# BrainA1-11Nov2014.net
KiCad netlist of a schematic drawn in EAGLE
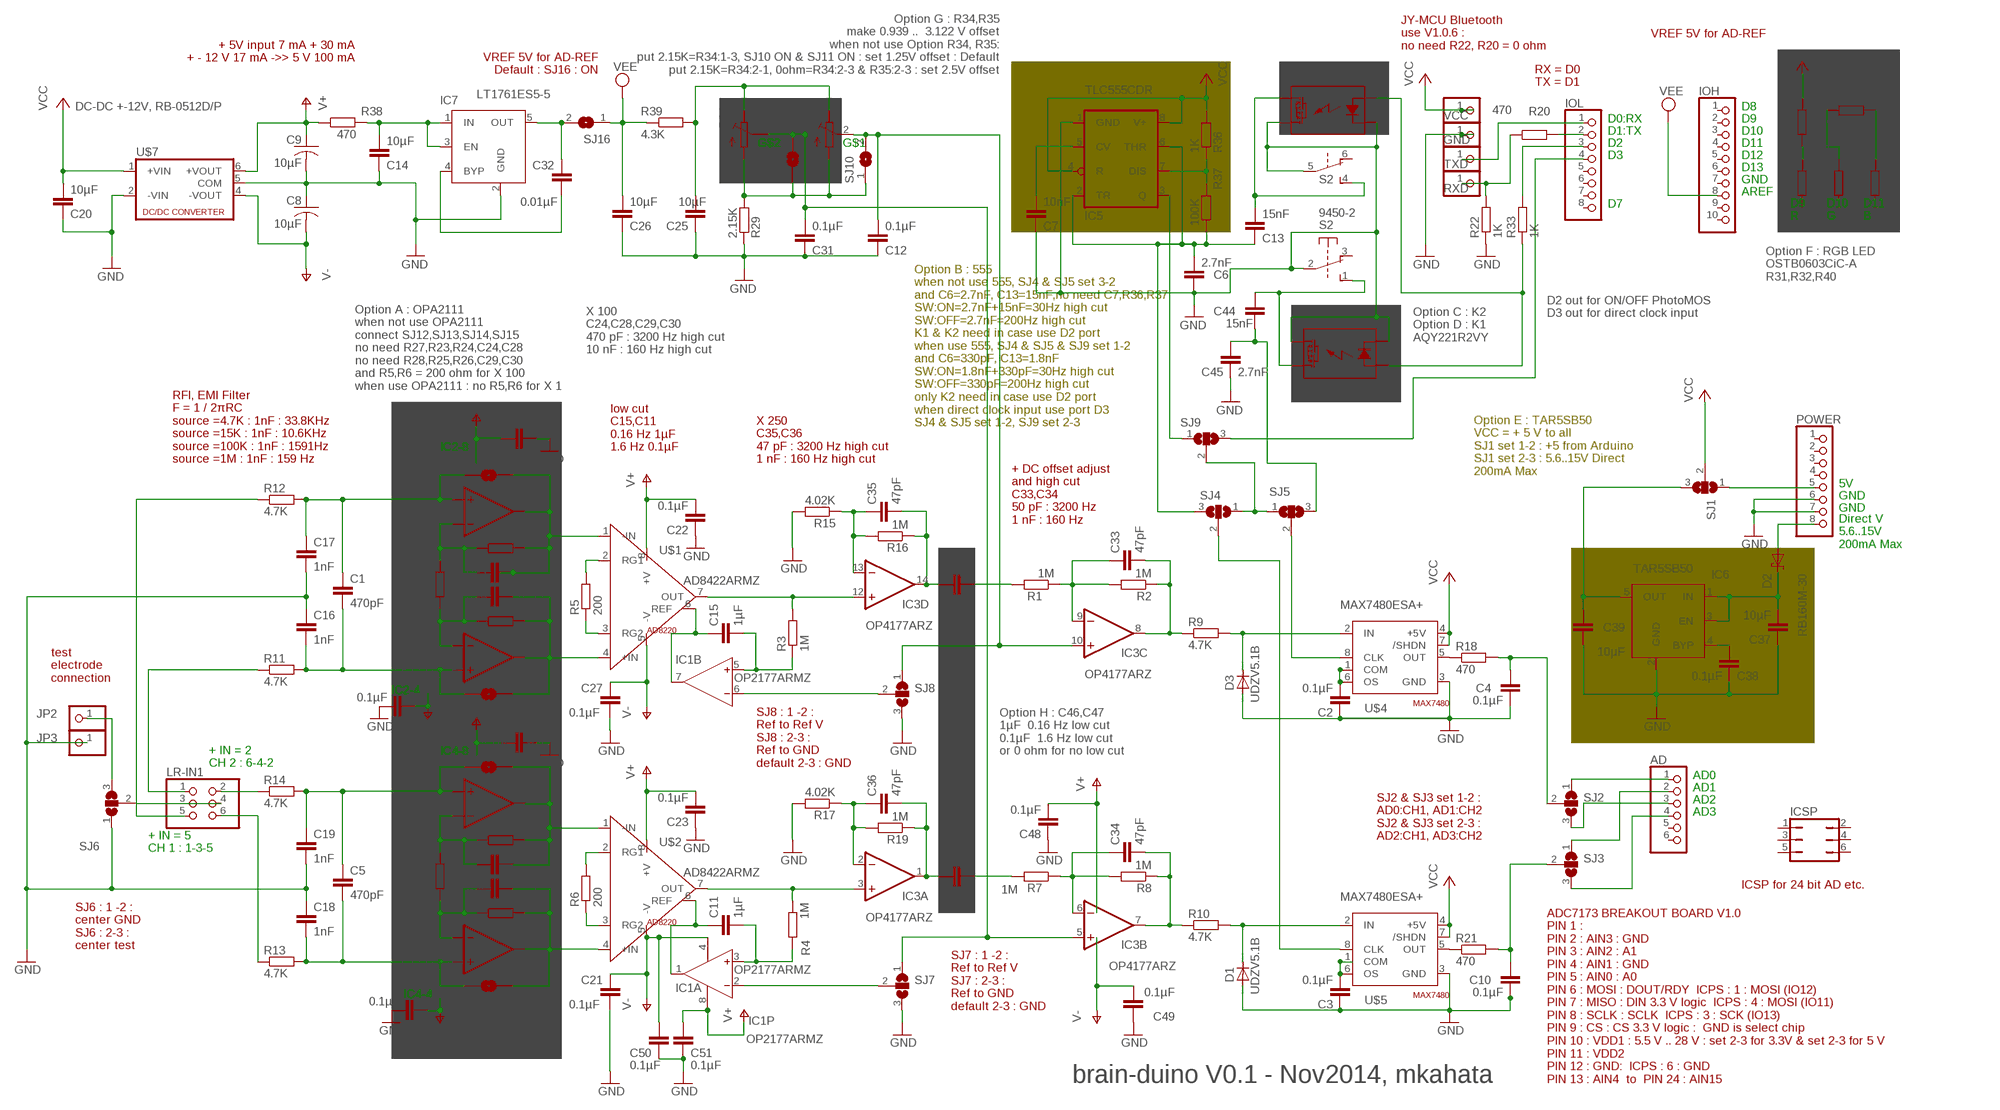
[diagram p0: schematic, sheet 1]

(export (version "E")
  (design (tool "Eeschema 10.0.6"))
  (components
    (comp (ref "AD")
      (value "PINHD-1X6")
      (footprint "eagle-import:1X06")
      (libsource (lib "eagle-import") (part "PINHD-1X6"))
    )
    (comp (ref "C1")
      (value "470pF")
      (footprint "eagle-import:C0805")
      (libsource (lib "eagle-import") (part "C-EUC0805"))
    )
    (comp (ref "C2")
      (value "0.1µF")
      (footprint "eagle-import:C0805")
      (libsource (lib "eagle-import") (part "C-EUC0805"))
    )
    (comp (ref "C3")
      (value "0.1µF")
      (footprint "eagle-import:C0805")
      (libsource (lib "eagle-import") (part "C-EUC0805"))
    )
    (comp (ref "C4")
      (value "0.1µF")
      (footprint "eagle-import:C0805")
      (libsource (lib "eagle-import") (part "C-EUC0805"))
    )
    (comp (ref "C5")
      (value "470pF")
      (footprint "eagle-import:C0805")
      (libsource (lib "eagle-import") (part "C-EUC0805"))
    )
    (comp (ref "C6")
      (value "2.7nF")
      (footprint "eagle-import:C0805")
      (libsource (lib "eagle-import") (part "C-EUC0805"))
    )
    (comp (ref "C7")
      (value "10nF")
      (footprint "eagle-import:C0805")
      (libsource (lib "eagle-import") (part "C-EUC0805"))
    )
    (comp (ref "C8")
      (value "10µF")
      (footprint "eagle-import:C0805")
      (libsource (lib "eagle-import") (part "C-USC0805"))
    )
    (comp (ref "C9")
      (value "10µF")
      (footprint "eagle-import:C0805")
      (libsource (lib "eagle-import") (part "C-USC0805"))
    )
    (comp (ref "C10")
      (value "0.1µF")
      (footprint "eagle-import:C0805")
      (libsource (lib "eagle-import") (part "C-EUC0805"))
    )
    (comp (ref "C11")
      (value "1µF")
      (footprint "eagle-import:C0805")
      (libsource (lib "eagle-import") (part "C-EUC0805"))
    )
    (comp (ref "C12")
      (value "0.1µF")
      (footprint "eagle-import:C0805")
      (libsource (lib "eagle-import") (part "C-EUC0805"))
    )
    (comp (ref "C13")
      (value "15nF")
      (footprint "eagle-import:C0805")
      (libsource (lib "eagle-import") (part "C-EUC0805"))
    )
    (comp (ref "C14")
      (value "10µF")
      (footprint "eagle-import:C0805")
      (libsource (lib "eagle-import") (part "C-EUC0805"))
    )
    (comp (ref "C15")
      (value "1µF")
      (footprint "eagle-import:C0805")
      (libsource (lib "eagle-import") (part "C-EUC0805"))
    )
    (comp (ref "C16")
      (value "1nF")
      (footprint "eagle-import:C0805")
      (libsource (lib "eagle-import") (part "C-EUC0805"))
    )
    (comp (ref "C17")
      (value "1nF")
      (footprint "eagle-import:C0805")
      (libsource (lib "eagle-import") (part "C-EUC0805"))
    )
    (comp (ref "C18")
      (value "1nF")
      (footprint "eagle-import:C0805")
      (libsource (lib "eagle-import") (part "C-EUC0805"))
    )
    (comp (ref "C19")
      (value "1nF")
      (footprint "eagle-import:C0805")
      (libsource (lib "eagle-import") (part "C-EUC0805"))
    )
    (comp (ref "C20")
      (value "10µF")
      (footprint "eagle-import:C0805")
      (libsource (lib "eagle-import") (part "C-EUC0805"))
    )
    (comp (ref "C21")
      (value "0.1µF")
      (footprint "eagle-import:C0805")
      (libsource (lib "eagle-import") (part "C-EUC0805"))
    )
    (comp (ref "C22")
      (value "0.1µF")
      (footprint "eagle-import:C0805")
      (libsource (lib "eagle-import") (part "C-EUC0805"))
    )
    (comp (ref "C23")
      (value "0.1µF")
      (footprint "eagle-import:C0805")
      (libsource (lib "eagle-import") (part "C-EUC0805"))
    )
    (comp (ref "C24")
      (value "470pF")
      (footprint "eagle-import:C0805")
      (libsource (lib "eagle-import") (part "C-EUC0805"))
    )
    (comp (ref "C25")
      (value "10µF")
      (footprint "eagle-import:C0805")
      (libsource (lib "eagle-import") (part "C-EUC0805"))
    )
    (comp (ref "C26")
      (value "10µF")
      (footprint "eagle-import:C0805")
      (libsource (lib "eagle-import") (part "C-EUC0805"))
    )
    (comp (ref "C27")
      (value "0.1µF")
      (footprint "eagle-import:C0805")
      (libsource (lib "eagle-import") (part "C-EUC0805"))
    )
    (comp (ref "C28")
      (value "470pF")
      (footprint "eagle-import:C0805")
      (libsource (lib "eagle-import") (part "C-EUC0805"))
    )
    (comp (ref "C29")
      (value "470pF")
      (footprint "eagle-import:C0805")
      (libsource (lib "eagle-import") (part "C-EUC0805"))
    )
    (comp (ref "C30")
      (value "470pF")
      (footprint "eagle-import:C0805")
      (libsource (lib "eagle-import") (part "C-EUC0805"))
    )
    (comp (ref "C31")
      (value "0.1µF")
      (footprint "eagle-import:C0805")
      (libsource (lib "eagle-import") (part "C-EUC0805"))
    )
    (comp (ref "C32")
      (value "0.01µF")
      (footprint "eagle-import:C0805")
      (libsource (lib "eagle-import") (part "C-EUC0805"))
    )
    (comp (ref "C33")
      (value "47pF")
      (footprint "eagle-import:C0805")
      (libsource (lib "eagle-import") (part "C-EUC0805"))
    )
    (comp (ref "C34")
      (value "47pF")
      (footprint "eagle-import:C0805")
      (libsource (lib "eagle-import") (part "C-EUC0805"))
    )
    (comp (ref "C35")
      (value "47pF")
      (footprint "eagle-import:C0805")
      (libsource (lib "eagle-import") (part "C-EUC0805"))
    )
    (comp (ref "C36")
      (value "47pF")
      (footprint "eagle-import:C0805")
      (libsource (lib "eagle-import") (part "C-EUC0805"))
    )
    (comp (ref "C37")
      (value "10µF")
      (footprint "eagle-import:C0805")
      (libsource (lib "eagle-import") (part "C-EUC0805"))
    )
    (comp (ref "C38")
      (value "0.1µF")
      (footprint "eagle-import:C0805")
      (libsource (lib "eagle-import") (part "C-EUC0805"))
    )
    (comp (ref "C39")
      (value "10µF")
      (footprint "eagle-import:C0805")
      (libsource (lib "eagle-import") (part "C-EUC0805"))
    )
    (comp (ref "C40")
      (value "0.1µF")
      (footprint "eagle-import:C0805")
      (libsource (lib "eagle-import") (part "C-EUC0805"))
    )
    (comp (ref "C41")
      (value "0.1µF")
      (footprint "eagle-import:C0805")
      (libsource (lib "eagle-import") (part "C-EUC0805"))
    )
    (comp (ref "C42")
      (value "0.1µF")
      (footprint "eagle-import:C0805")
      (libsource (lib "eagle-import") (part "C-EUC0805"))
    )
    (comp (ref "C43")
      (value "0.1µF")
      (footprint "eagle-import:C0805")
      (libsource (lib "eagle-import") (part "C-EUC0805"))
    )
    (comp (ref "C44")
      (value "15nF")
      (footprint "eagle-import:C0805")
      (libsource (lib "eagle-import") (part "C-EUC0805"))
    )
    (comp (ref "C45")
      (value "2.7nF")
      (footprint "eagle-import:C0805")
      (libsource (lib "eagle-import") (part "C-EUC0805"))
    )
    (comp (ref "C46")
      (value "1µF")
      (footprint "eagle-import:C0805")
      (libsource (lib "eagle-import") (part "C-EUC0805"))
    )
    (comp (ref "C47")
      (value "1µF")
      (footprint "eagle-import:C0805")
      (libsource (lib "eagle-import") (part "C-EUC0805"))
    )
    (comp (ref "C48")
      (value "0.1µF")
      (footprint "eagle-import:C0805")
      (libsource (lib "eagle-import") (part "C-EUC0805"))
    )
    (comp (ref "C49")
      (value "0.1µF")
      (footprint "eagle-import:C0805")
      (libsource (lib "eagle-import") (part "C-EUC0805"))
    )
    (comp (ref "C50")
      (value "0.1µF")
      (footprint "eagle-import:C0805")
      (libsource (lib "eagle-import") (part "C-EUC0805"))
    )
    (comp (ref "C51")
      (value "0.1µF")
      (footprint "eagle-import:C0805")
      (libsource (lib "eagle-import") (part "C-EUC0805"))
    )
    (comp (ref "D1")
      (value "UDZV5.1B")
      (footprint "eagle-import:SOD110-R")
      (libsource (lib "eagle-import") (part "DIODE-SOD110-R"))
    )
    (comp (ref "D2")
      (value "RB160M-30")
      (footprint "eagle-import:POWERDI323")
      (libsource (lib "eagle-import") (part "PD3S160"))
    )
    (comp (ref "D3")
      (value "UDZV5.1B")
      (footprint "eagle-import:SOD110-R")
      (libsource (lib "eagle-import") (part "DIODE-SOD110-R"))
    )
    (comp (ref "GND")
      (value "PINHD-1X1")
      (footprint "eagle-import:1X01")
      (libsource (lib "eagle-import") (part "PINHD-1X1"))
    )
    (comp (ref "IC1")
      (value "OP2177ARMZ")
      (footprint "eagle-import:MSOP08")
      (fields (field (name "MPN") "AD8656ARMZ"))
      (libsource (lib "eagle-import") (part "AD8656RM"))
    )
    (comp (ref "IC2")
      (value "OPA2111KP")
      (footprint "eagle-import:DIL08")
      (libsource (lib "eagle-import") (part "OPA2111P"))
    )
    (comp (ref "IC3")
      (value "OP4177ARZ")
      (footprint "eagle-import:SO14")
      (libsource (lib "eagle-import") (part "TL064D"))
    )
    (comp (ref "IC4")
      (value "OPA2111KP")
      (footprint "eagle-import:DIL08")
      (libsource (lib "eagle-import") (part "OPA2111P"))
    )
    (comp (ref "IC5")
      (value "TLC555CDR")
      (footprint "eagle-import:SO08")
      (libsource (lib "eagle-import") (part "555DLM"))
    )
    (comp (ref "IC6")
      (value "TAR5SB50")
      (footprint "eagle-import:SOT23-5")
      (libsource (lib "eagle-import") (part "MIC5219XX"))
    )
    (comp (ref "IC7")
      (value "LT1761ES5-5")
      (footprint "eagle-import:SOT23-5")
      (libsource (lib "eagle-import") (part "MIC5219XX"))
    )
    (comp (ref "ICSP")
      (value "JP3Q")
      (footprint "eagle-import:JP3Q")
      (libsource (lib "eagle-import") (part "JP3Q"))
    )
    (comp (ref "IOH")
      (value "PINHD-1X10")
      (footprint "eagle-import:1X10")
      (libsource (lib "eagle-import") (part "PINHD-1X10"))
    )
    (comp (ref "IOL")
      (value "PINHD-1X8")
      (footprint "eagle-import:1X08")
      (libsource (lib "eagle-import") (part "PINHD-1X8"))
    )
    (comp (ref "JP2")
      (value "PINHD-1X1")
      (footprint "eagle-import:1X01")
      (libsource (lib "eagle-import") (part "PINHD-1X1"))
    )
    (comp (ref "JP3")
      (value "PINHD-1X1")
      (footprint "eagle-import:1X01")
      (libsource (lib "eagle-import") (part "PINHD-1X1"))
    )
    (comp (ref "K1")
      (value "AQY221R2VY")
      (footprint "eagle-import:SSOP4")
      (fields (field (name "MF") "AROMAT/ MATSUSHITA") (field (name "MPN") "AQY221R2V"))
      (libsource (lib "eagle-import") (part "AQY2212VR"))
    )
    (comp (ref "K2")
      (value "AQY221R2VY")
      (footprint "eagle-import:SSOP4")
      (fields (field (name "MF") "AROMAT/ MATSUSHITA") (field (name "MPN") "AQY221R2V"))
      (libsource (lib "eagle-import") (part "AQY2212VR"))
    )
    (comp (ref "LR-IN1")
      (value "PINHD-2X3/90")
      (footprint "eagle-import:2X03_90")
      (libsource (lib "eagle-import") (part "PINHD-2X3/90"))
    )
    (comp (ref "POWER")
      (value "PINHD-1X8")
      (footprint "eagle-import:1X08")
      (libsource (lib "eagle-import") (part "PINHD-1X8"))
    )
    (comp (ref "R1")
      (value "1M")
      (footprint "eagle-import:R0805")
      (libsource (lib "eagle-import") (part "R-EU_R0805"))
    )
    (comp (ref "R2")
      (value "1M")
      (footprint "eagle-import:R0805")
      (libsource (lib "eagle-import") (part "R-EU_R0805"))
    )
    (comp (ref "R3")
      (value "1M")
      (footprint "eagle-import:R0805")
      (libsource (lib "eagle-import") (part "R-EU_R0805"))
    )
    (comp (ref "R4")
      (value "1M")
      (footprint "eagle-import:R0805")
      (libsource (lib "eagle-import") (part "R-EU_R0805"))
    )
    (comp (ref "R5")
      (value "200")
      (footprint "eagle-import:R0805")
      (libsource (lib "eagle-import") (part "R-EU_R0805"))
    )
    (comp (ref "R6")
      (value "200")
      (footprint "eagle-import:R0805")
      (libsource (lib "eagle-import") (part "R-EU_R0805"))
    )
    (comp (ref "R7")
      (value "1M")
      (footprint "eagle-import:R0805")
      (libsource (lib "eagle-import") (part "R-EU_R0805"))
    )
    (comp (ref "R8")
      (value "1M")
      (footprint "eagle-import:R0805")
      (libsource (lib "eagle-import") (part "R-EU_R0805"))
    )
    (comp (ref "R9")
      (value "4.7K")
      (footprint "eagle-import:R0805")
      (libsource (lib "eagle-import") (part "R-EU_R0805"))
    )
    (comp (ref "R10")
      (value "4.7K")
      (footprint "eagle-import:R0805")
      (libsource (lib "eagle-import") (part "R-EU_R0805"))
    )
    (comp (ref "R11")
      (value "4.7K")
      (footprint "eagle-import:R0805")
      (libsource (lib "eagle-import") (part "R-EU_R0805"))
    )
    (comp (ref "R12")
      (value "4.7K")
      (footprint "eagle-import:R0805")
      (libsource (lib "eagle-import") (part "R-EU_R0805"))
    )
    (comp (ref "R13")
      (value "4.7K")
      (footprint "eagle-import:R0805")
      (libsource (lib "eagle-import") (part "R-EU_R0805"))
    )
    (comp (ref "R14")
      (value "4.7K")
      (footprint "eagle-import:R0805")
      (libsource (lib "eagle-import") (part "R-EU_R0805"))
    )
    (comp (ref "R15")
      (value "4.02K")
      (footprint "eagle-import:R0805")
      (libsource (lib "eagle-import") (part "R-EU_R0805"))
    )
    (comp (ref "R16")
      (value "1M")
      (footprint "eagle-import:R0805")
      (libsource (lib "eagle-import") (part "R-EU_R0805"))
    )
    (comp (ref "R17")
      (value "4.02K")
      (footprint "eagle-import:R0805")
      (libsource (lib "eagle-import") (part "R-EU_R0805"))
    )
    (comp (ref "R18")
      (value "470")
      (footprint "eagle-import:R0805")
      (libsource (lib "eagle-import") (part "R-EU_R0805"))
    )
    (comp (ref "R19")
      (value "1M")
      (footprint "eagle-import:R0805")
      (libsource (lib "eagle-import") (part "R-EU_R0805"))
    )
    (comp (ref "R20")
      (value "470")
      (footprint "eagle-import:R0805")
      (libsource (lib "eagle-import") (part "R-EU_R0805"))
    )
    (comp (ref "R21")
      (value "470")
      (footprint "eagle-import:R0805")
      (libsource (lib "eagle-import") (part "R-EU_R0805"))
    )
    (comp (ref "R22")
      (value "1K")
      (footprint "eagle-import:R0805")
      (libsource (lib "eagle-import") (part "R-EU_R0805"))
    )
    (comp (ref "R23")
      (value "100K")
      (footprint "eagle-import:R0805")
      (libsource (lib "eagle-import") (part "R-EU_R0805"))
    )
    (comp (ref "R24")
      (value "100K")
      (footprint "eagle-import:R0805")
      (libsource (lib "eagle-import") (part "R-EU_R0805"))
    )
    (comp (ref "R25")
      (value "100K")
      (footprint "eagle-import:R0805")
      (libsource (lib "eagle-import") (part "R-EU_R0805"))
    )
    (comp (ref "R26")
      (value "100K")
      (footprint "eagle-import:R0805")
      (libsource (lib "eagle-import") (part "R-EU_R0805"))
    )
    (comp (ref "R27")
      (value "2K")
      (footprint "eagle-import:R0805")
      (libsource (lib "eagle-import") (part "R-EU_R0805"))
    )
    (comp (ref "R28")
      (value "2K")
      (footprint "eagle-import:R0805")
      (libsource (lib "eagle-import") (part "R-EU_R0805"))
    )
    (comp (ref "R29")
      (value "2.15K")
      (footprint "eagle-import:R0805")
      (libsource (lib "eagle-import") (part "R-EU_R0805"))
    )
    (comp (ref "R30")
      (value "LED")
      (footprint "eagle-import:R0402")
      (libsource (lib "eagle-import") (part "R-EU_R0402"))
    )
    (comp (ref "R31")
      (value "1K")
      (footprint "eagle-import:R0402")
      (libsource (lib "eagle-import") (part "R-EU_R0402"))
    )
    (comp (ref "R32")
      (value "1K")
      (footprint "eagle-import:R0402")
      (libsource (lib "eagle-import") (part "R-EU_R0402"))
    )
    (comp (ref "R33")
      (value "1K")
      (footprint "eagle-import:R0805")
      (libsource (lib "eagle-import") (part "R-EU_R0805"))
    )
    (comp (ref "R34")
      (value "10K")
      (footprint "eagle-import:RTRIM5X")
      (libsource (lib "eagle-import") (part "R-TRIMM5X"))
    )
    (comp (ref "R35")
      (value "10K")
      (footprint "eagle-import:RTRIM5X")
      (libsource (lib "eagle-import") (part "R-TRIMM5X"))
    )
    (comp (ref "R36")
      (value "1K")
      (footprint "eagle-import:R0805")
      (libsource (lib "eagle-import") (part "R-EU_R0805"))
    )
    (comp (ref "R37")
      (value "100K")
      (footprint "eagle-import:R0805")
      (libsource (lib "eagle-import") (part "R-EU_R0805"))
    )
    (comp (ref "R38")
      (value "470")
      (footprint "eagle-import:R0805")
      (libsource (lib "eagle-import") (part "R-EU_R0805"))
    )
    (comp (ref "R39")
      (value "4.3K")
      (footprint "eagle-import:R0805")
      (libsource (lib "eagle-import") (part "R-EU_R0805"))
    )
    (comp (ref "R40")
      (value "1K")
      (footprint "eagle-import:R0402")
      (libsource (lib "eagle-import") (part "R-EU_R0402"))
    )
    (comp (ref "R41")
      (value "LED")
      (footprint "eagle-import:R0402")
      (libsource (lib "eagle-import") (part "R-EU_R0402"))
    )
    (comp (ref "RXD")
      (value "PINHD-1X1")
      (footprint "eagle-import:1X01")
      (libsource (lib "eagle-import") (part "PINHD-1X1"))
    )
    (comp (ref "S2")
      (value "9450-2")
      (footprint "eagle-import:9450-2")
      (libsource (lib "eagle-import") (part "9450-2"))
    )
    (comp (ref "SJ1")
      (value "SJ2W")
      (footprint "eagle-import:SJ_2")
      (libsource (lib "eagle-import") (part "SJ2W"))
    )
    (comp (ref "SJ2")
      (value "SJ2W")
      (footprint "eagle-import:SJ_2")
      (libsource (lib "eagle-import") (part "SJ2W"))
    )
    (comp (ref "SJ3")
      (value "SJ2W")
      (footprint "eagle-import:SJ_2")
      (libsource (lib "eagle-import") (part "SJ2W"))
    )
    (comp (ref "SJ4")
      (value "SJ2W")
      (footprint "eagle-import:SJ_2")
      (libsource (lib "eagle-import") (part "SJ2W"))
    )
    (comp (ref "SJ5")
      (value "SJ2W")
      (footprint "eagle-import:SJ_2")
      (libsource (lib "eagle-import") (part "SJ2W"))
    )
    (comp (ref "SJ6")
      (value "SJ2W")
      (footprint "eagle-import:SJ_2")
      (libsource (lib "eagle-import") (part "SJ2W"))
    )
    (comp (ref "SJ7")
      (value "SJ2W")
      (footprint "eagle-import:SJ_2")
      (libsource (lib "eagle-import") (part "SJ2W"))
    )
    (comp (ref "SJ8")
      (value "SJ2W")
      (footprint "eagle-import:SJ_2")
      (libsource (lib "eagle-import") (part "SJ2W"))
    )
    (comp (ref "SJ9")
      (value "SJ2W")
      (footprint "eagle-import:SJ_2")
      (libsource (lib "eagle-import") (part "SJ2W"))
    )
    (comp (ref "SJ10")
      (value "SJ")
      (footprint "eagle-import:SJ")
      (libsource (lib "eagle-import") (part "SJ"))
    )
    (comp (ref "SJ11")
      (value "SJ")
      (footprint "eagle-import:SJ")
      (libsource (lib "eagle-import") (part "SJ"))
    )
    (comp (ref "SJ12")
      (value "SJ")
      (footprint "eagle-import:SJ")
      (libsource (lib "eagle-import") (part "SJ"))
    )
    (comp (ref "SJ13")
      (value "SJ")
      (footprint "eagle-import:SJ")
      (libsource (lib "eagle-import") (part "SJ"))
    )
    (comp (ref "SJ14")
      (value "SJ")
      (footprint "eagle-import:SJ")
      (libsource (lib "eagle-import") (part "SJ"))
    )
    (comp (ref "SJ15")
      (value "SJ")
      (footprint "eagle-import:SJ")
      (libsource (lib "eagle-import") (part "SJ"))
    )
    (comp (ref "SJ16")
      (value "SJ")
      (footprint "eagle-import:SJ")
      (libsource (lib "eagle-import") (part "SJ"))
    )
    (comp (ref "TXD")
      (value "PINHD-1X1")
      (footprint "eagle-import:1X01")
      (libsource (lib "eagle-import") (part "PINHD-1X1"))
    )
    (comp (ref "U$1")
      (value "AD8422ARMZ")
      (footprint "eagle-import:AD8220")
      (libsource (lib "eagle-import") (part "AD8220"))
    )
    (comp (ref "U$2")
      (value "AD8422ARMZ")
      (footprint "eagle-import:AD8220")
      (libsource (lib "eagle-import") (part "AD8220"))
    )
    (comp (ref "U$4")
      (value "MAX7480ESA+")
      (footprint "eagle-import:MAX7480")
      (libsource (lib "eagle-import") (part "MAX7480"))
    )
    (comp (ref "U$5")
      (value "MAX7480ESA+")
      (footprint "eagle-import:MAX7480")
      (libsource (lib "eagle-import") (part "MAX7480"))
    )
    (comp (ref "U$7")
      (value "DC-DC +-12V, RB-0512D/P")
      (footprint "eagle-import:RB-0515D")
      (libsource (lib "eagle-import") (part "RB-0515D"))
    )
    (comp (ref "VCC")
      (value "PINHD-1X1")
      (footprint "eagle-import:1X01")
      (libsource (lib "eagle-import") (part "PINHD-1X1"))
    )
  )
  (nets
    (net (code "1") (name "GND") (class "Default")
      (node (ref "C10") (pin "1") (pinfunction "1_1") (pintype "passive"))
      (node (ref "C12") (pin "1") (pinfunction "1_1") (pintype "passive"))
      (node (ref "C14") (pin "1") (pinfunction "1_1") (pintype "passive"))
      (node (ref "C16") (pin "1") (pinfunction "1_1") (pintype "passive"))
      (node (ref "C17") (pin "2") (pinfunction "2_2") (pintype "passive"))
      (node (ref "C18") (pin "1") (pinfunction "1_1") (pintype "passive"))
      (node (ref "C19") (pin "2") (pinfunction "2_2") (pintype "passive"))
      (node (ref "C2") (pin "1") (pinfunction "1_1") (pintype "passive"))
      (node (ref "C20") (pin "1") (pinfunction "1_1") (pintype "passive"))
      (node (ref "C21") (pin "2") (pinfunction "2_2") (pintype "passive"))
      (node (ref "C22") (pin "1") (pinfunction "1_1") (pintype "passive"))
      (node (ref "C23") (pin "1") (pinfunction "1_1") (pintype "passive"))
      (node (ref "C25") (pin "1") (pinfunction "1_1") (pintype "passive"))
      (node (ref "C26") (pin "1") (pinfunction "1_1") (pintype "passive"))
      (node (ref "C27") (pin "2") (pinfunction "2_2") (pintype "passive"))
      (node (ref "C3") (pin "1") (pinfunction "1_1") (pintype "passive"))
      (node (ref "C31") (pin "1") (pinfunction "1_1") (pintype "passive"))
      (node (ref "C37") (pin "1") (pinfunction "1_1") (pintype "passive"))
      (node (ref "C38") (pin "1") (pinfunction "1_1") (pintype "passive"))
      (node (ref "C39") (pin "1") (pinfunction "1_1") (pintype "passive"))
      (node (ref "C4") (pin "1") (pinfunction "1_1") (pintype "passive"))
      (node (ref "C40") (pin "1") (pinfunction "1_1") (pintype "passive"))
      (node (ref "C41") (pin "2") (pinfunction "2_2") (pintype "passive"))
      (node (ref "C42") (pin "2") (pinfunction "2_2") (pintype "passive"))
      (node (ref "C43") (pin "2") (pinfunction "2_2") (pintype "passive"))
      (node (ref "C45") (pin "1") (pinfunction "1_1") (pintype "passive"))
      (node (ref "C48") (pin "1") (pinfunction "1_1") (pintype "passive"))
      (node (ref "C49") (pin "1") (pinfunction "1_1") (pintype "passive"))
      (node (ref "C50") (pin "2") (pinfunction "2_2") (pintype "passive"))
      (node (ref "C51") (pin "2") (pinfunction "2_2") (pintype "passive"))
      (node (ref "C6") (pin "1") (pinfunction "1_1") (pintype "passive"))
      (node (ref "C7") (pin "1") (pinfunction "1_1") (pintype "passive"))
      (node (ref "C8") (pin "1") (pinfunction "1_1") (pintype "passive"))
      (node (ref "C9") (pin "2") (pinfunction "2_2") (pintype "passive"))
      (node (ref "D1") (pin "A") (pinfunction "A_A") (pintype "passive"))
      (node (ref "D3") (pin "A") (pinfunction "A_A") (pintype "passive"))
      (node (ref "GND") (pin "1") (pinfunction "1_1") (pintype "passive"))
      (node (ref "IC5") (pin "1") (pinfunction "GND_1") (pintype "power_in"))
      (node (ref "IC6") (pin "2") (pinfunction "GND_2") (pintype "power_in"))
      (node (ref "IC7") (pin "2") (pinfunction "GND_2") (pintype "power_in"))
      (node (ref "JP3") (pin "1") (pinfunction "1_1") (pintype "passive"))
      (node (ref "K1") (pin "2") (pinfunction "K_2") (pintype "passive"))
      (node (ref "K1") (pin "3") (pinfunction "DS2_3") (pintype "passive"))
      (node (ref "K2") (pin "2") (pinfunction "K_2") (pintype "passive"))
      (node (ref "K2") (pin "3") (pinfunction "DS2_3") (pintype "passive"))
      (node (ref "POWER") (pin "6") (pinfunction "6_6") (pintype "passive"))
      (node (ref "POWER") (pin "7") (pinfunction "7_7") (pintype "passive"))
      (node (ref "R15") (pin "2") (pinfunction "2_2") (pintype "passive"))
      (node (ref "R17") (pin "2") (pinfunction "2_2") (pintype "passive"))
      (node (ref "R22") (pin "1") (pinfunction "1_1") (pintype "passive"))
      (node (ref "R29") (pin "1") (pinfunction "1_1") (pintype "passive"))
      (node (ref "S2") (pin "2") (pinfunction "P_2") (pintype "passive"))
      (node (ref "S2") (pin "5") (pinfunction "P_5") (pintype "passive"))
      (node (ref "SJ6") (pin "1") (pinfunction "1_1") (pintype "passive"))
      (node (ref "SJ7") (pin "3") (pinfunction "3_3") (pintype "passive"))
      (node (ref "SJ8") (pin "3") (pinfunction "3_3") (pintype "passive"))
      (node (ref "U$4") (pin "3") (pinfunction "GND_3") (pintype "power_in"))
      (node (ref "U$5") (pin "3") (pinfunction "GND_3") (pintype "power_in"))
      (node (ref "U$7") (pin "2") (pinfunction "-VIN_2") (pintype "passive"))
      (node (ref "U$7") (pin "5") (pinfunction "COM_5") (pintype "passive"))
    )
    (net (code "2") (name "Net-(AD-Pad1)") (class "Default")
      (node (ref "AD") (pin "1") (pinfunction "1_1") (pintype "passive"))
      (node (ref "SJ2") (pin "1") (pinfunction "1_1") (pintype "passive"))
    )
    (net (code "3") (name "Net-(AD-Pad2)") (class "Default")
      (node (ref "AD") (pin "2") (pinfunction "2_2") (pintype "passive"))
      (node (ref "SJ3") (pin "1") (pinfunction "1_1") (pintype "passive"))
    )
    (net (code "4") (name "Net-(AD-Pad3)") (class "Default")
      (node (ref "AD") (pin "3") (pinfunction "3_3") (pintype "passive"))
      (node (ref "SJ2") (pin "3") (pinfunction "3_3") (pintype "passive"))
    )
    (net (code "5") (name "Net-(AD-Pad4)") (class "Default")
      (node (ref "AD") (pin "4") (pinfunction "4_4") (pintype "passive"))
      (node (ref "SJ3") (pin "3") (pinfunction "3_3") (pintype "passive"))
    )
    (net (code "6") (name "Net-(C4-Pad2)") (class "Default")
      (node (ref "C4") (pin "2") (pinfunction "2_2") (pintype "passive"))
      (node (ref "R18") (pin "2") (pinfunction "2_2") (pintype "passive"))
      (node (ref "SJ2") (pin "2") (pinfunction "2_2") (pintype "passive"))
    )
    (net (code "7") (name "Net-(C10-Pad2)") (class "Default")
      (node (ref "C10") (pin "2") (pinfunction "2_2") (pintype "passive"))
      (node (ref "R21") (pin "2") (pinfunction "2_2") (pintype "passive"))
      (node (ref "SJ3") (pin "2") (pinfunction "2_2") (pintype "passive"))
    )
    (net (code "8") (name "Net-(C44-Pad1)") (class "Default")
      (node (ref "C44") (pin "1") (pinfunction "1_1") (pintype "passive"))
      (node (ref "C45") (pin "2") (pinfunction "2_2") (pintype "passive"))
      (node (ref "SJ5") (pin "3") (pinfunction "3_3") (pintype "passive"))
    )
    (net (code "9") (name "Net-(C46-Pad2)") (class "Default")
      (node (ref "C46") (pin "2") (pinfunction "2_2") (pintype "passive"))
      (node (ref "R1") (pin "2") (pinfunction "2_2") (pintype "passive"))
    )
    (net (code "10") (name "Net-(C47-Pad2)") (class "Default")
      (node (ref "C47") (pin "2") (pinfunction "2_2") (pintype "passive"))
      (node (ref "R7") (pin "2") (pinfunction "2_2") (pintype "passive"))
    )
    (net (code "11") (name "Net-(D2-PadA)") (class "Default")
      (node (ref "D2") (pin "A") (pinfunction "A_A") (pintype "passive"))
      (node (ref "POWER") (pin "8") (pinfunction "8_8") (pintype "passive"))
    )
    (net (code "12") (name "Net-(IC1A-IN+)") (class "Default")
      (node (ref "C11") (pin "2") (pinfunction "2_2") (pintype "passive"))
      (node (ref "IC1") (pin "3") (pinfunction "IN+_3") (pintype "input"))
      (node (ref "R4") (pin "1") (pinfunction "1_1") (pintype "passive"))
    )
    (net (code "13") (name "Net-(IC1A-IN-)") (class "Default")
      (node (ref "IC1") (pin "2") (pinfunction "IN-_2") (pintype "input"))
      (node (ref "SJ7") (pin "2") (pinfunction "2_2") (pintype "passive"))
    )
    (net (code "14") (name "Net-(IC1A-OUT)") (class "Default")
      (node (ref "C11") (pin "1") (pinfunction "1_1") (pintype "passive"))
      (node (ref "IC1") (pin "1") (pinfunction "OUT_1") (pintype "output"))
      (node (ref "U$2") (pin "6") (pinfunction "REF_6") (pintype "input"))
    )
    (net (code "15") (name "Net-(IC1B-IN+)") (class "Default")
      (node (ref "C15") (pin "2") (pinfunction "2_2") (pintype "passive"))
      (node (ref "IC1") (pin "5") (pinfunction "IN+_5") (pintype "input"))
      (node (ref "R3") (pin "1") (pinfunction "1_1") (pintype "passive"))
    )
    (net (code "16") (name "Net-(IC1B-IN-)") (class "Default")
      (node (ref "IC1") (pin "6") (pinfunction "IN-_6") (pintype "input"))
      (node (ref "SJ8") (pin "2") (pinfunction "2_2") (pintype "passive"))
    )
    (net (code "17") (name "Net-(IC1B-OUT)") (class "Default")
      (node (ref "C15") (pin "1") (pinfunction "1_1") (pintype "passive"))
      (node (ref "IC1") (pin "7") (pinfunction "OUT_7") (pintype "output"))
      (node (ref "U$1") (pin "6") (pinfunction "REF_6") (pintype "input"))
    )
    (net (code "18") (name "Net-(IC2A-+IN)") (class "Default")
      (node (ref "C1") (pin "1") (pinfunction "1_1") (pintype "passive"))
      (node (ref "C17") (pin "1") (pinfunction "1_1") (pintype "passive"))
      (node (ref "IC2") (pin "3") (pinfunction "+IN_3") (pintype "input"))
      (node (ref "R12") (pin "2") (pinfunction "2_2") (pintype "passive"))
      (node (ref "SJ12") (pin "2") (pinfunction "2_2") (pintype "passive"))
    )
    (net (code "19") (name "Net-(IC2A--IN)") (class "Default")
      (node (ref "C24") (pin "1") (pinfunction "1_1") (pintype "passive"))
      (node (ref "IC2") (pin "2") (pinfunction "-IN_2") (pintype "input"))
      (node (ref "R23") (pin "1") (pinfunction "1_1") (pintype "passive"))
      (node (ref "R27") (pin "2") (pinfunction "2_2") (pintype "passive"))
    )
    (net (code "20") (name "Net-(IC2A-OUT)") (class "Default")
      (node (ref "C24") (pin "2") (pinfunction "2_2") (pintype "passive"))
      (node (ref "IC2") (pin "1") (pinfunction "OUT_1") (pintype "output"))
      (node (ref "R23") (pin "2") (pinfunction "2_2") (pintype "passive"))
      (node (ref "SJ12") (pin "1") (pinfunction "1_1") (pintype "passive"))
      (node (ref "U$1") (pin "1") (pinfunction "-IN_1") (pintype "input"))
    )
    (net (code "21") (name "Net-(IC2B-+IN)") (class "Default")
      (node (ref "C1") (pin "2") (pinfunction "2_2") (pintype "passive"))
      (node (ref "C16") (pin "2") (pinfunction "2_2") (pintype "passive"))
      (node (ref "IC2") (pin "5") (pinfunction "+IN_5") (pintype "input"))
      (node (ref "R11") (pin "2") (pinfunction "2_2") (pintype "passive"))
      (node (ref "SJ13") (pin "2") (pinfunction "2_2") (pintype "passive"))
    )
    (net (code "22") (name "Net-(IC2B--IN)") (class "Default")
      (node (ref "C28") (pin "1") (pinfunction "1_1") (pintype "passive"))
      (node (ref "IC2") (pin "6") (pinfunction "-IN_6") (pintype "input"))
      (node (ref "R24") (pin "1") (pinfunction "1_1") (pintype "passive"))
      (node (ref "R27") (pin "1") (pinfunction "1_1") (pintype "passive"))
    )
    (net (code "23") (name "Net-(IC2B-OUT)") (class "Default")
      (node (ref "C28") (pin "2") (pinfunction "2_2") (pintype "passive"))
      (node (ref "IC2") (pin "7") (pinfunction "OUT_7") (pintype "output"))
      (node (ref "R24") (pin "2") (pinfunction "2_2") (pintype "passive"))
      (node (ref "SJ13") (pin "1") (pinfunction "1_1") (pintype "passive"))
      (node (ref "U$1") (pin "4") (pinfunction "+IN_4") (pintype "passive"))
    )
    (net (code "24") (name "Net-(IC3A-+IN)") (class "Default")
      (node (ref "IC3") (pin "3") (pinfunction "+IN_3") (pintype "input"))
      (node (ref "R4") (pin "2") (pinfunction "2_2") (pintype "passive"))
      (node (ref "U$2") (pin "7") (pinfunction "OUT_7") (pintype "input"))
    )
    (net (code "25") (name "Net-(IC3A--IN)") (class "Default")
      (node (ref "C36") (pin "1") (pinfunction "1_1") (pintype "passive"))
      (node (ref "IC3") (pin "2") (pinfunction "-IN_2") (pintype "input"))
      (node (ref "R17") (pin "1") (pinfunction "1_1") (pintype "passive"))
      (node (ref "R19") (pin "2") (pinfunction "2_2") (pintype "passive"))
    )
    (net (code "26") (name "Net-(IC3A-OUT)") (class "Default")
      (node (ref "C36") (pin "2") (pinfunction "2_2") (pintype "passive"))
      (node (ref "C47") (pin "1") (pinfunction "1_1") (pintype "passive"))
      (node (ref "IC3") (pin "1") (pinfunction "OUT_1") (pintype "output"))
      (node (ref "R19") (pin "1") (pinfunction "1_1") (pintype "passive"))
    )
    (net (code "27") (name "Net-(IC3B-+IN)") (class "Default")
      (node (ref "C31") (pin "2") (pinfunction "2_2") (pintype "passive"))
      (node (ref "IC3") (pin "5") (pinfunction "+IN_5") (pintype "input"))
      (node (ref "R34") (pin "2") (pinfunction "S_2") (pintype "passive"))
      (node (ref "SJ11") (pin "2") (pinfunction "2_2") (pintype "passive"))
      (node (ref "SJ7") (pin "1") (pinfunction "1_1") (pintype "passive"))
    )
    (net (code "28") (name "Net-(IC3B--IN)") (class "Default")
      (node (ref "C34") (pin "1") (pinfunction "1_1") (pintype "passive"))
      (node (ref "IC3") (pin "6") (pinfunction "-IN_6") (pintype "input"))
      (node (ref "R7") (pin "1") (pinfunction "1_1") (pintype "passive"))
      (node (ref "R8") (pin "2") (pinfunction "2_2") (pintype "passive"))
    )
    (net (code "29") (name "Net-(IC3B-OUT)") (class "Default")
      (node (ref "C34") (pin "2") (pinfunction "2_2") (pintype "passive"))
      (node (ref "IC3") (pin "7") (pinfunction "OUT_7") (pintype "output"))
      (node (ref "R10") (pin "1") (pinfunction "1_1") (pintype "passive"))
      (node (ref "R8") (pin "1") (pinfunction "1_1") (pintype "passive"))
    )
    (net (code "30") (name "Net-(IC3C-+IN)") (class "Default")
      (node (ref "C12") (pin "2") (pinfunction "2_2") (pintype "passive"))
      (node (ref "IC3") (pin "10") (pinfunction "+IN_10") (pintype "input"))
      (node (ref "R35") (pin "2") (pinfunction "S_2") (pintype "passive"))
      (node (ref "SJ10") (pin "2") (pinfunction "2_2") (pintype "passive"))
      (node (ref "SJ8") (pin "1") (pinfunction "1_1") (pintype "passive"))
    )
    (net (code "31") (name "Net-(IC3C--IN)") (class "Default")
      (node (ref "C33") (pin "1") (pinfunction "1_1") (pintype "passive"))
      (node (ref "IC3") (pin "9") (pinfunction "-IN_9") (pintype "input"))
      (node (ref "R1") (pin "1") (pinfunction "1_1") (pintype "passive"))
      (node (ref "R2") (pin "2") (pinfunction "2_2") (pintype "passive"))
    )
    (net (code "32") (name "Net-(IC3C-OUT)") (class "Default")
      (node (ref "C33") (pin "2") (pinfunction "2_2") (pintype "passive"))
      (node (ref "IC3") (pin "8") (pinfunction "OUT_8") (pintype "output"))
      (node (ref "R2") (pin "1") (pinfunction "1_1") (pintype "passive"))
      (node (ref "R9") (pin "1") (pinfunction "1_1") (pintype "passive"))
    )
    (net (code "33") (name "Net-(IC3D-+IN)") (class "Default")
      (node (ref "IC3") (pin "12") (pinfunction "+IN_12") (pintype "input"))
      (node (ref "R3") (pin "2") (pinfunction "2_2") (pintype "passive"))
      (node (ref "U$1") (pin "7") (pinfunction "OUT_7") (pintype "input"))
    )
    (net (code "34") (name "Net-(IC3D--IN)") (class "Default")
      (node (ref "C35") (pin "1") (pinfunction "1_1") (pintype "passive"))
      (node (ref "IC3") (pin "13") (pinfunction "-IN_13") (pintype "input"))
      (node (ref "R15") (pin "1") (pinfunction "1_1") (pintype "passive"))
      (node (ref "R16") (pin "2") (pinfunction "2_2") (pintype "passive"))
    )
    (net (code "35") (name "Net-(IC3D-OUT)") (class "Default")
      (node (ref "C35") (pin "2") (pinfunction "2_2") (pintype "passive"))
      (node (ref "C46") (pin "1") (pinfunction "1_1") (pintype "passive"))
      (node (ref "IC3") (pin "14") (pinfunction "OUT_14") (pintype "output"))
      (node (ref "R16") (pin "1") (pinfunction "1_1") (pintype "passive"))
    )
    (net (code "36") (name "Net-(IC4A-+IN)") (class "Default")
      (node (ref "C19") (pin "1") (pinfunction "1_1") (pintype "passive"))
      (node (ref "C5") (pin "1") (pinfunction "1_1") (pintype "passive"))
      (node (ref "IC4") (pin "3") (pinfunction "+IN_3") (pintype "input"))
      (node (ref "R14") (pin "2") (pinfunction "2_2") (pintype "passive"))
      (node (ref "SJ14") (pin "2") (pinfunction "2_2") (pintype "passive"))
    )
    (net (code "37") (name "Net-(IC4A--IN)") (class "Default")
      (node (ref "C29") (pin "1") (pinfunction "1_1") (pintype "passive"))
      (node (ref "IC4") (pin "2") (pinfunction "-IN_2") (pintype "input"))
      (node (ref "R25") (pin "1") (pinfunction "1_1") (pintype "passive"))
      (node (ref "R28") (pin "2") (pinfunction "2_2") (pintype "passive"))
    )
    (net (code "38") (name "Net-(IC4A-OUT)") (class "Default")
      (node (ref "C29") (pin "2") (pinfunction "2_2") (pintype "passive"))
      (node (ref "IC4") (pin "1") (pinfunction "OUT_1") (pintype "output"))
      (node (ref "R25") (pin "2") (pinfunction "2_2") (pintype "passive"))
      (node (ref "SJ14") (pin "1") (pinfunction "1_1") (pintype "passive"))
      (node (ref "U$2") (pin "1") (pinfunction "-IN_1") (pintype "input"))
    )
    (net (code "39") (name "Net-(IC4B-+IN)") (class "Default")
      (node (ref "C18") (pin "2") (pinfunction "2_2") (pintype "passive"))
      (node (ref "C5") (pin "2") (pinfunction "2_2") (pintype "passive"))
      (node (ref "IC4") (pin "5") (pinfunction "+IN_5") (pintype "input"))
      (node (ref "R13") (pin "2") (pinfunction "2_2") (pintype "passive"))
      (node (ref "SJ15") (pin "2") (pinfunction "2_2") (pintype "passive"))
    )
    (net (code "40") (name "Net-(IC4B--IN)") (class "Default")
      (node (ref "C30") (pin "1") (pinfunction "1_1") (pintype "passive"))
      (node (ref "IC4") (pin "6") (pinfunction "-IN_6") (pintype "input"))
      (node (ref "R26") (pin "1") (pinfunction "1_1") (pintype "passive"))
      (node (ref "R28") (pin "1") (pinfunction "1_1") (pintype "passive"))
    )
    (net (code "41") (name "Net-(IC4B-OUT)") (class "Default")
      (node (ref "C30") (pin "2") (pinfunction "2_2") (pintype "passive"))
      (node (ref "IC4") (pin "7") (pinfunction "OUT_7") (pintype "output"))
      (node (ref "R26") (pin "2") (pinfunction "2_2") (pintype "passive"))
      (node (ref "SJ15") (pin "1") (pinfunction "1_1") (pintype "passive"))
      (node (ref "U$2") (pin "4") (pinfunction "+IN_4") (pintype "passive"))
    )
    (net (code "42") (name "Net-(IC5-CV)") (class "Default")
      (node (ref "C7") (pin "2") (pinfunction "2_2") (pintype "passive"))
      (node (ref "IC5") (pin "5") (pinfunction "CV_5") (pintype "input"))
    )
    (net (code "43") (name "Net-(IC5-DIS)") (class "Default")
      (node (ref "IC5") (pin "7") (pinfunction "DIS_7") (pintype "input"))
      (node (ref "R36") (pin "1") (pinfunction "1_1") (pintype "passive"))
      (node (ref "R37") (pin "2") (pinfunction "2_2") (pintype "passive"))
    )
    (net (code "44") (name "Net-(IC5-Q)") (class "Default")
      (node (ref "IC5") (pin "3") (pinfunction "Q_3") (pintype "output"))
      (node (ref "SJ9") (pin "1") (pinfunction "1_1") (pintype "passive"))
    )
    (net (code "45") (name "Net-(IC5-THR)") (class "Default")
      (node (ref "C13") (pin "1") (pinfunction "1_1") (pintype "passive"))
      (node (ref "C6") (pin "2") (pinfunction "2_2") (pintype "passive"))
      (node (ref "IC5") (pin "2") (pinfunction "TR_2") (pintype "input"))
      (node (ref "IC5") (pin "6") (pinfunction "THR_6") (pintype "input"))
      (node (ref "R37") (pin "1") (pinfunction "1_1") (pintype "passive"))
      (node (ref "SJ4") (pin "3") (pinfunction "3_3") (pintype "passive"))
    )
    (net (code "46") (name "Net-(IC6-BYP)") (class "Default")
      (node (ref "C38") (pin "2") (pinfunction "2_2") (pintype "passive"))
      (node (ref "IC6") (pin "4") (pinfunction "BYP_4") (pintype "passive"))
    )
    (net (code "47") (name "Net-(IC6-EN)") (class "Default")
      (node (ref "C37") (pin "2") (pinfunction "2_2") (pintype "passive"))
      (node (ref "D2") (pin "C") (pinfunction "C_C") (pintype "passive"))
      (node (ref "IC6") (pin "1") (pinfunction "IN_1") (pintype "input"))
      (node (ref "IC6") (pin "3") (pinfunction "EN_3") (pintype "input"))
    )
    (net (code "48") (name "Net-(IC6-OUT)") (class "Default")
      (node (ref "C39") (pin "2") (pinfunction "2_2") (pintype "passive"))
      (node (ref "IC6") (pin "5") (pinfunction "OUT_5") (pintype "output"))
      (node (ref "SJ1") (pin "3") (pinfunction "3_3") (pintype "passive"))
    )
    (net (code "49") (name "Net-(IC7-BYP)") (class "Default")
      (node (ref "C32") (pin "1") (pinfunction "1_1") (pintype "passive"))
      (node (ref "IC7") (pin "4") (pinfunction "BYP_4") (pintype "passive"))
    )
    (net (code "50") (name "Net-(IC7-EN)") (class "Default")
      (node (ref "C14") (pin "2") (pinfunction "2_2") (pintype "passive"))
      (node (ref "IC7") (pin "1") (pinfunction "IN_1") (pintype "input"))
      (node (ref "IC7") (pin "3") (pinfunction "EN_3") (pintype "input"))
      (node (ref "R38") (pin "2") (pinfunction "2_2") (pintype "passive"))
    )
    (net (code "51") (name "Net-(IC7-OUT)") (class "Default")
      (node (ref "C32") (pin "2") (pinfunction "2_2") (pintype "passive"))
      (node (ref "IC7") (pin "5") (pinfunction "OUT_5") (pintype "output"))
      (node (ref "SJ16") (pin "2") (pinfunction "2_2") (pintype "passive"))
    )
    (net (code "52") (name "Net-(IOL-Pad1)") (class "Default")
      (node (ref "IOL") (pin "1") (pinfunction "1_1") (pintype "passive"))
      (node (ref "TXD") (pin "1") (pinfunction "1_1") (pintype "passive"))
    )
    (net (code "53") (name "Net-(IOL-Pad2)") (class "Default")
      (node (ref "IOL") (pin "2") (pinfunction "2_2") (pintype "passive"))
      (node (ref "R20") (pin "2") (pinfunction "2_2") (pintype "passive"))
    )
    (net (code "54") (name "Net-(IOL-Pad3)") (class "Default")
      (node (ref "IOL") (pin "3") (pinfunction "3_3") (pintype "passive"))
      (node (ref "R33") (pin "2") (pinfunction "2_2") (pintype "passive"))
    )
    (net (code "55") (name "Net-(IOL-Pad4)") (class "Default")
      (node (ref "IOL") (pin "4") (pinfunction "4_4") (pintype "passive"))
      (node (ref "SJ9") (pin "3") (pinfunction "3_3") (pintype "passive"))
    )
    (net (code "56") (name "Net-(JP2-Pad1)") (class "Default")
      (node (ref "JP2") (pin "1") (pinfunction "1_1") (pintype "passive"))
      (node (ref "SJ6") (pin "3") (pinfunction "3_3") (pintype "passive"))
    )
    (net (code "57") (name "Net-(K1-A)") (class "Default")
      (node (ref "K1") (pin "1") (pinfunction "A_1") (pintype "passive"))
      (node (ref "K2") (pin "1") (pinfunction "A_1") (pintype "passive"))
      (node (ref "R33") (pin "1") (pinfunction "1_1") (pintype "passive"))
    )
    (net (code "58") (name "Net-(K1-DS1)") (class "Default")
      (node (ref "C44") (pin "2") (pinfunction "2_2") (pintype "passive"))
      (node (ref "K1") (pin "4") (pinfunction "DS1_4") (pintype "passive"))
      (node (ref "S2") (pin "1") (pinfunction "S_1") (pintype "passive"))
    )
    (net (code "59") (name "Net-(K2-DS1)") (class "Default")
      (node (ref "C13") (pin "2") (pinfunction "2_2") (pintype "passive"))
      (node (ref "K2") (pin "4") (pinfunction "DS1_4") (pintype "passive"))
      (node (ref "S2") (pin "4") (pinfunction "S_4") (pintype "passive"))
    )
    (net (code "60") (name "Net-(LR-IN1-Pad1)") (class "Default")
      (node (ref "LR-IN1") (pin "1") (pinfunction "1_1") (pintype "passive"))
      (node (ref "R11") (pin "1") (pinfunction "1_1") (pintype "passive"))
    )
    (net (code "61") (name "Net-(LR-IN1-Pad2)") (class "Default")
      (node (ref "LR-IN1") (pin "2") (pinfunction "2_2") (pintype "passive"))
      (node (ref "R14") (pin "1") (pinfunction "1_1") (pintype "passive"))
    )
    (net (code "62") (name "Net-(LR-IN1-Pad3)") (class "Default")
      (node (ref "LR-IN1") (pin "3") (pinfunction "3_3") (pintype "passive"))
      (node (ref "LR-IN1") (pin "4") (pinfunction "4_4") (pintype "passive"))
      (node (ref "SJ6") (pin "2") (pinfunction "2_2") (pintype "passive"))
    )
    (net (code "63") (name "Net-(LR-IN1-Pad5)") (class "Default")
      (node (ref "LR-IN1") (pin "5") (pinfunction "5_5") (pintype "passive"))
      (node (ref "R12") (pin "1") (pinfunction "1_1") (pintype "passive"))
    )
    (net (code "64") (name "Net-(LR-IN1-Pad6)") (class "Default")
      (node (ref "LR-IN1") (pin "6") (pinfunction "6_6") (pintype "passive"))
      (node (ref "R13") (pin "1") (pinfunction "1_1") (pintype "passive"))
    )
    (net (code "65") (name "Net-(POWER-Pad5)") (class "Default")
      (node (ref "POWER") (pin "5") (pinfunction "5_5") (pintype "passive"))
      (node (ref "SJ1") (pin "1") (pinfunction "1_1") (pintype "passive"))
    )
    (net (code "66") (name "Net-(R20-Pad1)") (class "Default")
      (node (ref "R20") (pin "1") (pinfunction "1_1") (pintype "passive"))
      (node (ref "R22") (pin "2") (pinfunction "2_2") (pintype "passive"))
      (node (ref "RXD") (pin "1") (pinfunction "1_1") (pintype "passive"))
    )
    (net (code "67") (name "Net-(R30-Pad1)") (class "Default")
      (node (ref "R30") (pin "1") (pinfunction "1_1") (pintype "passive"))
      (node (ref "R40") (pin "2") (pinfunction "2_2") (pintype "passive"))
    )
    (net (code "68") (name "Net-(R30-Pad2)") (class "Default")
      (node (ref "R30") (pin "2") (pinfunction "2_2") (pintype "passive"))
      (node (ref "R32") (pin "2") (pinfunction "2_2") (pintype "passive"))
    )
    (net (code "69") (name "Net-(R31-Pad2)") (class "Default")
      (node (ref "R31") (pin "2") (pinfunction "2_2") (pintype "passive"))
      (node (ref "R41") (pin "1") (pinfunction "1_1") (pintype "passive"))
    )
    (net (code "70") (name "Net-(R34-A)") (class "Default")
      (node (ref "C25") (pin "2") (pinfunction "2_2") (pintype "passive"))
      (node (ref "R34") (pin "3") (pinfunction "A_3") (pintype "passive"))
      (node (ref "R35") (pin "3") (pinfunction "A_3") (pintype "passive"))
      (node (ref "R39") (pin "2") (pinfunction "2_2") (pintype "passive"))
    )
    (net (code "71") (name "Net-(R34-E)") (class "Default")
      (node (ref "R29") (pin "2") (pinfunction "2_2") (pintype "passive"))
      (node (ref "R34") (pin "1") (pinfunction "E_1") (pintype "passive"))
      (node (ref "R35") (pin "1") (pinfunction "E_1") (pintype "passive"))
      (node (ref "SJ10") (pin "1") (pinfunction "1_1") (pintype "passive"))
      (node (ref "SJ11") (pin "1") (pinfunction "1_1") (pintype "passive"))
    )
    (net (code "72") (name "Net-(SJ4-Pad1)") (class "Default")
      (node (ref "SJ4") (pin "1") (pinfunction "1_1") (pintype "passive"))
      (node (ref "SJ5") (pin "1") (pinfunction "1_1") (pintype "passive"))
      (node (ref "SJ9") (pin "2") (pinfunction "2_2") (pintype "passive"))
    )
    (net (code "73") (name "Net-(U$1-RG1)") (class "Default")
      (node (ref "R5") (pin "2") (pinfunction "2_2") (pintype "passive"))
      (node (ref "U$1") (pin "2") (pinfunction "RG1_2") (pintype "input"))
    )
    (net (code "74") (name "Net-(U$1-RG2)") (class "Default")
      (node (ref "R5") (pin "1") (pinfunction "1_1") (pintype "passive"))
      (node (ref "U$1") (pin "3") (pinfunction "RG2_3") (pintype "input"))
    )
    (net (code "75") (name "Net-(U$2-RG1)") (class "Default")
      (node (ref "R6") (pin "2") (pinfunction "2_2") (pintype "passive"))
      (node (ref "U$2") (pin "2") (pinfunction "RG1_2") (pintype "input"))
    )
    (net (code "76") (name "Net-(U$2-RG2)") (class "Default")
      (node (ref "R6") (pin "1") (pinfunction "1_1") (pintype "passive"))
      (node (ref "U$2") (pin "3") (pinfunction "RG2_3") (pintype "input"))
    )
    (net (code "77") (name "Net-(U$4-CLK)") (class "Default")
      (node (ref "SJ5") (pin "2") (pinfunction "2_2") (pintype "passive"))
      (node (ref "U$4") (pin "8") (pinfunction "CLK_8") (pintype "input"))
    )
    (net (code "78") (name "Net-(U$4-COM)") (class "Default")
      (node (ref "C2") (pin "2") (pinfunction "2_2") (pintype "passive"))
      (node (ref "U$4") (pin "1") (pinfunction "COM_1") (pintype "input"))
      (node (ref "U$4") (pin "6") (pinfunction "OS_6") (pintype "passive"))
    )
    (net (code "79") (name "Net-(U$4-IN)") (class "Default")
      (node (ref "D3") (pin "C") (pinfunction "C_C") (pintype "passive"))
      (node (ref "R9") (pin "2") (pinfunction "2_2") (pintype "passive"))
      (node (ref "U$4") (pin "2") (pinfunction "IN_2") (pintype "input"))
    )
    (net (code "80") (name "Net-(U$4-OUT)") (class "Default")
      (node (ref "R18") (pin "1") (pinfunction "1_1") (pintype "passive"))
      (node (ref "U$4") (pin "5") (pinfunction "OUT_5") (pintype "input"))
    )
    (net (code "81") (name "Net-(U$5-CLK)") (class "Default")
      (node (ref "SJ4") (pin "2") (pinfunction "2_2") (pintype "passive"))
      (node (ref "U$5") (pin "8") (pinfunction "CLK_8") (pintype "input"))
    )
    (net (code "82") (name "Net-(U$5-COM)") (class "Default")
      (node (ref "C3") (pin "2") (pinfunction "2_2") (pintype "passive"))
      (node (ref "U$5") (pin "1") (pinfunction "COM_1") (pintype "input"))
      (node (ref "U$5") (pin "6") (pinfunction "OS_6") (pintype "passive"))
    )
    (net (code "83") (name "Net-(U$5-IN)") (class "Default")
      (node (ref "D1") (pin "C") (pinfunction "C_C") (pintype "passive"))
      (node (ref "R10") (pin "2") (pinfunction "2_2") (pintype "passive"))
      (node (ref "U$5") (pin "2") (pinfunction "IN_2") (pintype "input"))
    )
    (net (code "84") (name "Net-(U$5-OUT)") (class "Default")
      (node (ref "R21") (pin "1") (pinfunction "1_1") (pintype "passive"))
      (node (ref "U$5") (pin "5") (pinfunction "OUT_5") (pintype "input"))
    )
    (net (code "85") (name "V+") (class "Default")
      (node (ref "C22") (pin "2") (pinfunction "2_2") (pintype "passive"))
      (node (ref "C23") (pin "2") (pinfunction "2_2") (pintype "passive"))
      (node (ref "C40") (pin "2") (pinfunction "2_2") (pintype "passive"))
      (node (ref "C42") (pin "1") (pinfunction "1_1") (pintype "passive"))
      (node (ref "C48") (pin "2") (pinfunction "2_2") (pintype "passive"))
      (node (ref "C51") (pin "1") (pinfunction "1_1") (pintype "passive"))
      (node (ref "C9") (pin "1") (pinfunction "1_1") (pintype "passive"))
      (node (ref "IC1") (pin "8") (pinfunction "V+_8") (pintype "power_in"))
      (node (ref "R38") (pin "1") (pinfunction "1_1") (pintype "passive"))
      (node (ref "U$1") (pin "8") (pinfunction "+V_8") (pintype "power_in"))
      (node (ref "U$2") (pin "8") (pinfunction "+V_8") (pintype "power_in"))
      (node (ref "U$7") (pin "6") (pinfunction "+VOUT_6") (pintype "passive"))
    )
    (net (code "86") (name "V-") (class "Default")
      (node (ref "C21") (pin "1") (pinfunction "1_1") (pintype "passive"))
      (node (ref "C27") (pin "1") (pinfunction "1_1") (pintype "passive"))
      (node (ref "C41") (pin "1") (pinfunction "1_1") (pintype "passive"))
      (node (ref "C43") (pin "1") (pinfunction "1_1") (pintype "passive"))
      (node (ref "C49") (pin "2") (pinfunction "2_2") (pintype "passive"))
      (node (ref "C50") (pin "1") (pinfunction "1_1") (pintype "passive"))
      (node (ref "C8") (pin "2") (pinfunction "2_2") (pintype "passive"))
      (node (ref "IC1") (pin "4") (pinfunction "V-_4") (pintype "power_in"))
      (node (ref "U$1") (pin "5") (pinfunction "-V_5") (pintype "power_in"))
      (node (ref "U$2") (pin "5") (pinfunction "-V_5") (pintype "power_in"))
      (node (ref "U$7") (pin "4") (pinfunction "-VOUT_4") (pintype "passive"))
    )
    (net (code "87") (name "VCC") (class "Default")
      (node (ref "C20") (pin "2") (pinfunction "2_2") (pintype "passive"))
      (node (ref "IC5") (pin "4") (pinfunction "R_4") (pintype "input"))
      (node (ref "IC5") (pin "8") (pinfunction "V+_8") (pintype "power_in"))
      (node (ref "R36") (pin "2") (pinfunction "2_2") (pintype "passive"))
      (node (ref "R41") (pin "2") (pinfunction "2_2") (pintype "passive"))
      (node (ref "SJ1") (pin "2") (pinfunction "2_2") (pintype "passive"))
      (node (ref "U$4") (pin "4") (pinfunction "+5V_4") (pintype "power_in"))
      (node (ref "U$4") (pin "7") (pinfunction "/SHDN_7") (pintype "input"))
      (node (ref "U$5") (pin "4") (pinfunction "+5V_4") (pintype "power_in"))
      (node (ref "U$5") (pin "7") (pinfunction "/SHDN_7") (pintype "input"))
      (node (ref "U$7") (pin "1") (pinfunction "+VIN_1") (pintype "passive"))
      (node (ref "VCC") (pin "1") (pinfunction "1_1") (pintype "passive"))
    )
    (net (code "88") (name "VEE") (class "Default")
      (node (ref "C26") (pin "2") (pinfunction "2_2") (pintype "passive"))
      (node (ref "IOH") (pin "8") (pinfunction "8_8") (pintype "passive"))
      (node (ref "R39") (pin "1") (pinfunction "1_1") (pintype "passive"))
      (node (ref "SJ16") (pin "1") (pinfunction "1_1") (pintype "passive"))
    )
    (net (code "89") (name "unconnected-(AD-Pad5)") (class "Default")
      (node (ref "AD") (pin "5") (pinfunction "5_5") (pintype "passive"))
    )
    (net (code "90") (name "unconnected-(AD-Pad6)") (class "Default")
      (node (ref "AD") (pin "6") (pinfunction "6_6") (pintype "passive"))
    )
    (net (code "91") (name "unconnected-(ICSP-Pad1)") (class "Default")
      (node (ref "ICSP") (pin "1") (pinfunction "1_1") (pintype "passive"))
    )
    (net (code "92") (name "unconnected-(ICSP-Pad2)") (class "Default")
      (node (ref "ICSP") (pin "2") (pinfunction "2_2") (pintype "passive"))
    )
    (net (code "93") (name "unconnected-(ICSP-Pad3)") (class "Default")
      (node (ref "ICSP") (pin "3") (pinfunction "3_3") (pintype "passive"))
    )
    (net (code "94") (name "unconnected-(ICSP-Pad4)") (class "Default")
      (node (ref "ICSP") (pin "4") (pinfunction "4_4") (pintype "passive"))
    )
    (net (code "95") (name "unconnected-(ICSP-Pad5)") (class "Default")
      (node (ref "ICSP") (pin "5") (pinfunction "5_5") (pintype "passive"))
    )
    (net (code "96") (name "unconnected-(ICSP-Pad6)") (class "Default")
      (node (ref "ICSP") (pin "6") (pinfunction "6_6") (pintype "passive"))
    )
    (net (code "97") (name "unconnected-(IOH-Pad1)") (class "Default")
      (node (ref "IOH") (pin "1") (pinfunction "1_1") (pintype "passive"))
    )
    (net (code "98") (name "unconnected-(IOH-Pad2)") (class "Default")
      (node (ref "IOH") (pin "2") (pinfunction "2_2") (pintype "passive"))
    )
    (net (code "99") (name "unconnected-(IOH-Pad3)") (class "Default")
      (node (ref "IOH") (pin "3") (pinfunction "3_3") (pintype "passive"))
    )
    (net (code "100") (name "unconnected-(IOH-Pad4)") (class "Default")
      (node (ref "IOH") (pin "4") (pinfunction "4_4") (pintype "passive"))
    )
    (net (code "101") (name "unconnected-(IOH-Pad5)") (class "Default")
      (node (ref "IOH") (pin "5") (pinfunction "5_5") (pintype "passive"))
    )
    (net (code "102") (name "unconnected-(IOH-Pad6)") (class "Default")
      (node (ref "IOH") (pin "6") (pinfunction "6_6") (pintype "passive"))
    )
    (net (code "103") (name "unconnected-(IOH-Pad7)") (class "Default")
      (node (ref "IOH") (pin "7") (pinfunction "7_7") (pintype "passive"))
    )
    (net (code "104") (name "unconnected-(IOH-Pad9)") (class "Default")
      (node (ref "IOH") (pin "9") (pinfunction "9_9") (pintype "passive"))
    )
    (net (code "105") (name "unconnected-(IOH-Pad10)") (class "Default")
      (node (ref "IOH") (pin "10") (pinfunction "10_10") (pintype "passive"))
    )
    (net (code "106") (name "unconnected-(IOL-Pad5)") (class "Default")
      (node (ref "IOL") (pin "5") (pinfunction "5_5") (pintype "passive"))
    )
    (net (code "107") (name "unconnected-(IOL-Pad6)") (class "Default")
      (node (ref "IOL") (pin "6") (pinfunction "6_6") (pintype "passive"))
    )
    (net (code "108") (name "unconnected-(IOL-Pad7)") (class "Default")
      (node (ref "IOL") (pin "7") (pinfunction "7_7") (pintype "passive"))
    )
    (net (code "109") (name "unconnected-(IOL-Pad8)") (class "Default")
      (node (ref "IOL") (pin "8") (pinfunction "8_8") (pintype "passive"))
    )
    (net (code "110") (name "unconnected-(POWER-Pad1)") (class "Default")
      (node (ref "POWER") (pin "1") (pinfunction "1_1") (pintype "passive"))
    )
    (net (code "111") (name "unconnected-(POWER-Pad2)") (class "Default")
      (node (ref "POWER") (pin "2") (pinfunction "2_2") (pintype "passive"))
    )
    (net (code "112") (name "unconnected-(POWER-Pad3)") (class "Default")
      (node (ref "POWER") (pin "3") (pinfunction "3_3") (pintype "passive"))
    )
    (net (code "113") (name "unconnected-(POWER-Pad4)") (class "Default")
      (node (ref "POWER") (pin "4") (pinfunction "4_4") (pintype "passive"))
    )
    (net (code "114") (name "unconnected-(R31-Pad1)") (class "Default")
      (node (ref "R31") (pin "1") (pinfunction "1_1") (pintype "passive"))
    )
    (net (code "115") (name "unconnected-(R32-Pad1)") (class "Default")
      (node (ref "R32") (pin "1") (pinfunction "1_1") (pintype "passive"))
    )
    (net (code "116") (name "unconnected-(R40-Pad1)") (class "Default")
      (node (ref "R40") (pin "1") (pinfunction "1_1") (pintype "passive"))
    )
    (net (code "117") (name "unconnected-(S2A-O-Pad3)") (class "Default")
      (node (ref "S2") (pin "3") (pinfunction "O_3") (pintype "passive"))
    )
    (net (code "118") (name "unconnected-(S2B-O-Pad6)") (class "Default")
      (node (ref "S2") (pin "6") (pinfunction "O_6") (pintype "passive"))
    )
  )
)
